# SMART_DISPENSER_RELAY.net
KiCad netlist of a schematic drawn in EAGLE
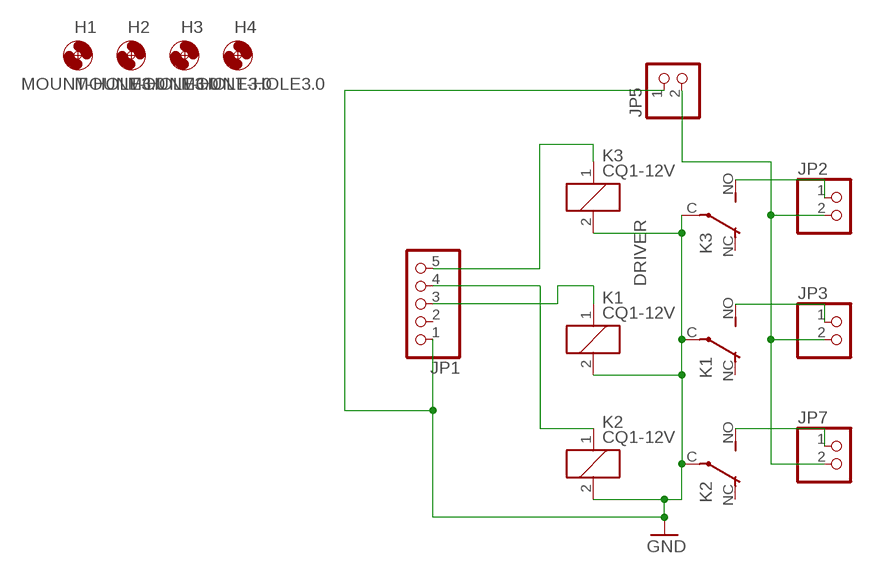
[diagram p0: schematic, sheet 1]

(export (version "E")
  (design (tool "Eeschema 10.0.6"))
  (components
    (comp (ref "H1")
      (value "MOUNT-HOLE3.0")
      (footprint "eagle-import:3,0")
      (libsource (lib "eagle-import") (part "MOUNT-HOLE3.0"))
    )
    (comp (ref "H2")
      (value "MOUNT-HOLE3.0")
      (footprint "eagle-import:3,0")
      (libsource (lib "eagle-import") (part "MOUNT-HOLE3.0"))
    )
    (comp (ref "H3")
      (value "MOUNT-HOLE3.0")
      (footprint "eagle-import:3,0")
      (libsource (lib "eagle-import") (part "MOUNT-HOLE3.0"))
    )
    (comp (ref "H4")
      (value "MOUNT-HOLE3.0")
      (footprint "eagle-import:3,0")
      (libsource (lib "eagle-import") (part "MOUNT-HOLE3.0"))
    )
    (comp (ref "JP1")
      (value "PINHD-1X5")
      (footprint "eagle-import:1X05")
      (libsource (lib "eagle-import") (part "PINHD-1X5"))
    )
    (comp (ref "JP2")
      (value "PINHD-1X2")
      (footprint "eagle-import:1X02")
      (libsource (lib "eagle-import") (part "PINHD-1X2"))
    )
    (comp (ref "JP3")
      (value "PINHD-1X2")
      (footprint "eagle-import:1X02")
      (libsource (lib "eagle-import") (part "PINHD-1X2"))
    )
    (comp (ref "JP5")
      (value "PINHD-1X2")
      (footprint "eagle-import:1X02")
      (libsource (lib "eagle-import") (part "PINHD-1X2"))
    )
    (comp (ref "JP7")
      (value "PINHD-1X2")
      (footprint "eagle-import:1X02")
      (libsource (lib "eagle-import") (part "PINHD-1X2"))
    )
    (comp (ref "K1")
      (value "CQ1-12V")
      (footprint "eagle-import:CQ1")
      (libsource (lib "eagle-import") (part "CQ1-12V"))
    )
    (comp (ref "K2")
      (value "CQ1-12V")
      (footprint "eagle-import:CQ1")
      (libsource (lib "eagle-import") (part "CQ1-12V"))
    )
    (comp (ref "K3")
      (value "CQ1-12V")
      (footprint "eagle-import:CQ1")
      (libsource (lib "eagle-import") (part "CQ1-12V"))
    )
  )
  (nets
    (net (code "1") (name "GND") (class "Default")
      (node (ref "JP1") (pin "1") (pinfunction "1_1") (pintype "passive"))
      (node (ref "JP5") (pin "1") (pinfunction "1_1") (pintype "passive"))
      (node (ref "K1") (pin "2") (pinfunction "2_2") (pintype "passive"))
      (node (ref "K1") (pin "C") (pinfunction "P_C") (pintype "passive"))
      (node (ref "K2") (pin "2") (pinfunction "2_2") (pintype "passive"))
      (node (ref "K2") (pin "C") (pinfunction "P_C") (pintype "passive"))
      (node (ref "K3") (pin "2") (pinfunction "2_2") (pintype "passive"))
      (node (ref "K3") (pin "C") (pinfunction "P_C") (pintype "passive"))
    )
    (net (code "2") (name "Net-(JP1-Pad3)") (class "Default")
      (node (ref "JP1") (pin "3") (pinfunction "3_3") (pintype "passive"))
      (node (ref "K1") (pin "1") (pinfunction "1_1") (pintype "passive"))
    )
    (net (code "3") (name "Net-(JP1-Pad4)") (class "Default")
      (node (ref "JP1") (pin "4") (pinfunction "4_4") (pintype "passive"))
      (node (ref "K2") (pin "1") (pinfunction "1_1") (pintype "passive"))
    )
    (net (code "4") (name "Net-(JP1-Pad5)") (class "Default")
      (node (ref "JP1") (pin "5") (pinfunction "5_5") (pintype "passive"))
      (node (ref "K3") (pin "1") (pinfunction "1_1") (pintype "passive"))
    )
    (net (code "5") (name "Net-(JP2-Pad2)") (class "Default")
      (node (ref "JP2") (pin "2") (pinfunction "2_2") (pintype "passive"))
      (node (ref "JP3") (pin "2") (pinfunction "2_2") (pintype "passive"))
      (node (ref "JP5") (pin "2") (pinfunction "2_2") (pintype "passive"))
      (node (ref "JP7") (pin "2") (pinfunction "2_2") (pintype "passive"))
    )
    (net (code "6") (name "Net-(K1B-S)") (class "Default")
      (node (ref "JP3") (pin "1") (pinfunction "1_1") (pintype "passive"))
      (node (ref "K1") (pin "NO") (pinfunction "S_NO") (pintype "passive"))
    )
    (net (code "7") (name "Net-(K2B-S)") (class "Default")
      (node (ref "JP7") (pin "1") (pinfunction "1_1") (pintype "passive"))
      (node (ref "K2") (pin "NO") (pinfunction "S_NO") (pintype "passive"))
    )
    (net (code "8") (name "Net-(K3B-S)") (class "Default")
      (node (ref "JP2") (pin "1") (pinfunction "1_1") (pintype "passive"))
      (node (ref "K3") (pin "NO") (pinfunction "S_NO") (pintype "passive"))
    )
    (net (code "9") (name "unconnected-(JP1-Pad2)") (class "Default")
      (node (ref "JP1") (pin "2") (pinfunction "2_2") (pintype "passive"))
    )
    (net (code "10") (name "unconnected-(K1B-O-PadNC)") (class "Default")
      (node (ref "K1") (pin "NC") (pinfunction "O_NC") (pintype "passive"))
    )
    (net (code "11") (name "unconnected-(K2B-O-PadNC)") (class "Default")
      (node (ref "K2") (pin "NC") (pinfunction "O_NC") (pintype "passive"))
    )
    (net (code "12") (name "unconnected-(K3B-O-PadNC)") (class "Default")
      (node (ref "K3") (pin "NC") (pinfunction "O_NC") (pintype "passive"))
    )
  )
)
